# Microcontroller_STM_STM32F373CC.net
KiCad netlist of a schematic drawn in EAGLE
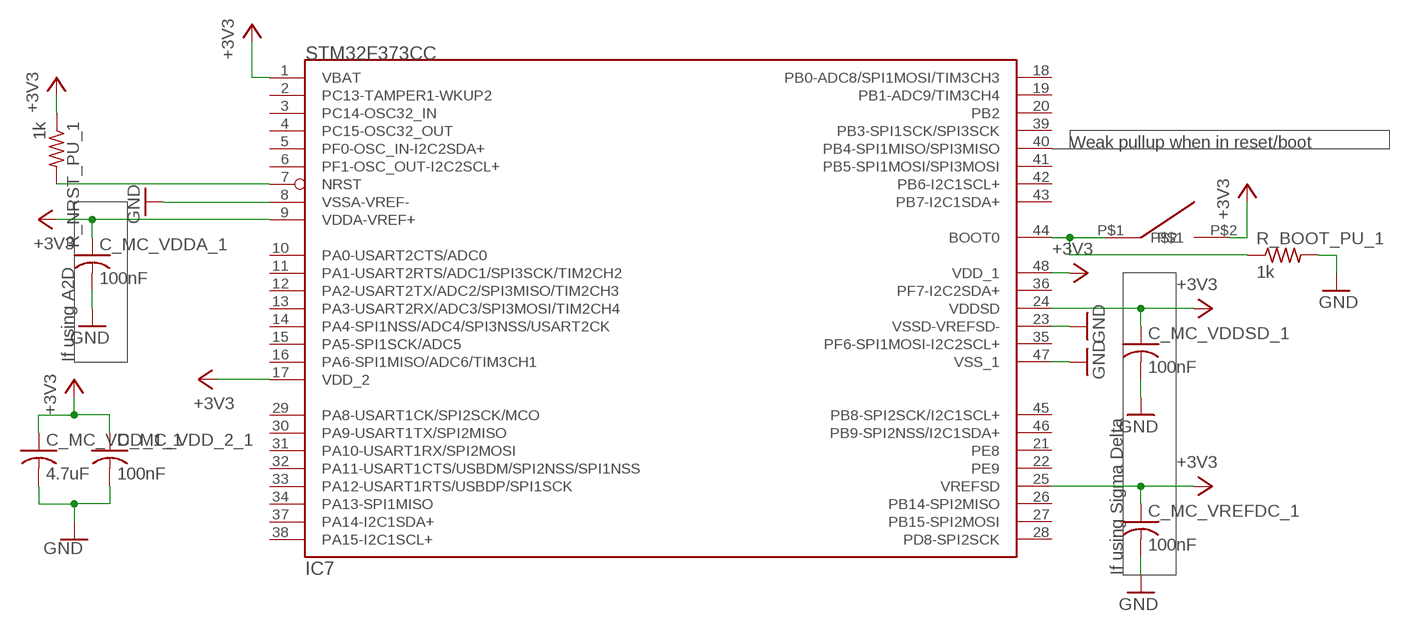
[diagram p0: schematic, sheet 1]

(export (version "E")
  (design (tool "Eeschema 10.0.6"))
  (components
    (comp (ref "C_MC_VDDA_1")
      (value "100nF")
      (footprint "eagle-import:C0603")
      (libsource (lib "eagle-import") (part "C-USC0603"))
    )
    (comp (ref "C_MC_VDDSD_1")
      (value "100nF")
      (footprint "eagle-import:C0603")
      (libsource (lib "eagle-import") (part "C-USC0603"))
    )
    (comp (ref "C_MC_VDD_1_1")
      (value "4.7uF")
      (footprint "eagle-import:C0603")
      (libsource (lib "eagle-import") (part "C-USC0603"))
    )
    (comp (ref "C_MC_VDD_2_1")
      (value "100nF")
      (footprint "eagle-import:C0603")
      (libsource (lib "eagle-import") (part "C-USC0603"))
    )
    (comp (ref "C_MC_VREFDC_1")
      (value "100nF")
      (footprint "eagle-import:C0603")
      (libsource (lib "eagle-import") (part "C-USC0603"))
    )
    (comp (ref "IC7")
      (value "STM32F373CC")
      (footprint "eagle-import:LQFP48")
      (libsource (lib "eagle-import") (part "STM32F373CC"))
    )
    (comp (ref "R_BOOT_PU_1")
      (value "1k")
      (footprint "eagle-import:R0603")
      (libsource (lib "eagle-import") (part "R-US_R0603"))
    )
    (comp (ref "R_NRST_PU_1")
      (value "1k")
      (footprint "eagle-import:R0603")
      (libsource (lib "eagle-import") (part "R-US_R0603"))
    )
    (comp (ref "SW1")
      (value "B3U")
      (footprint "eagle-import:B3U")
      (libsource (lib "eagle-import") (part "B3U"))
    )
  )
  (nets
    (net (code "1") (name "+3V3") (class "Default")
      (node (ref "C_MC_VDDA_1") (pin "1") (pinfunction "1_1") (pintype "passive"))
      (node (ref "C_MC_VDDSD_1") (pin "1") (pinfunction "1_1") (pintype "passive"))
      (node (ref "C_MC_VDD_1_1") (pin "1") (pinfunction "1_1") (pintype "passive"))
      (node (ref "C_MC_VDD_2_1") (pin "1") (pinfunction "1_1") (pintype "passive"))
      (node (ref "C_MC_VREFDC_1") (pin "1") (pinfunction "1_1") (pintype "passive"))
      (node (ref "IC7") (pin "1") (pinfunction "VBAT_1") (pintype "power_in"))
      (node (ref "IC7") (pin "17") (pinfunction "VDD_2_17") (pintype "bidirectional"))
      (node (ref "IC7") (pin "24") (pinfunction "VDDSD_24") (pintype "power_in"))
      (node (ref "IC7") (pin "25") (pinfunction "VREFSD_25") (pintype "bidirectional"))
      (node (ref "IC7") (pin "48") (pinfunction "VDD_1_48") (pintype "power_in"))
      (node (ref "IC7") (pin "9") (pinfunction "VDDA-VREF+_9") (pintype "power_in"))
      (node (ref "R_NRST_PU_1") (pin "1") (pinfunction "1_1") (pintype "passive"))
      (node (ref "SW1") (pin "P$2") (pinfunction "P$2_P$2") (pintype "bidirectional"))
    )
    (net (code "2") (name "GND") (class "Default")
      (node (ref "C_MC_VDDA_1") (pin "2") (pinfunction "2_2") (pintype "passive"))
      (node (ref "C_MC_VDDSD_1") (pin "2") (pinfunction "2_2") (pintype "passive"))
      (node (ref "C_MC_VDD_1_1") (pin "2") (pinfunction "2_2") (pintype "passive"))
      (node (ref "C_MC_VDD_2_1") (pin "2") (pinfunction "2_2") (pintype "passive"))
      (node (ref "C_MC_VREFDC_1") (pin "2") (pinfunction "2_2") (pintype "passive"))
      (node (ref "IC7") (pin "23") (pinfunction "VSSD-VREFSD-_23") (pintype "power_in"))
      (node (ref "IC7") (pin "47") (pinfunction "VSS_1_47") (pintype "power_in"))
      (node (ref "IC7") (pin "8") (pinfunction "VSSA-VREF-_8") (pintype "power_in"))
      (node (ref "R_BOOT_PU_1") (pin "2") (pinfunction "2_2") (pintype "passive"))
    )
    (net (code "3") (name "Net-(IC7-BOOT0)") (class "Default")
      (node (ref "IC7") (pin "44") (pinfunction "BOOT0_44") (pintype "input"))
      (node (ref "R_BOOT_PU_1") (pin "1") (pinfunction "1_1") (pintype "passive"))
      (node (ref "SW1") (pin "P$1") (pinfunction "P$1_P$1") (pintype "bidirectional"))
    )
    (net (code "4") (name "Net-(IC7-NRST)") (class "Default")
      (node (ref "IC7") (pin "7") (pinfunction "NRST_7") (pintype "bidirectional"))
      (node (ref "R_NRST_PU_1") (pin "2") (pinfunction "2_2") (pintype "passive"))
    )
    (net (code "5") (name "unconnected-(IC7-PA0-USART2CTS{slash}ADC0-Pad10)") (class "Default")
      (node (ref "IC7") (pin "10") (pinfunction "PA0-USART2CTS/ADC0_10") (pintype "bidirectional"))
    )
    (net (code "6") (name "unconnected-(IC7-PA1-USART2RTS{slash}ADC1{slash}SPI3SCK{slash}TIM2CH2-Pad11)") (class "Default")
      (node (ref "IC7") (pin "11") (pinfunction "PA1-USART2RTS/ADC1/SPI3SCK/TIM2CH2_11") (pintype "bidirectional"))
    )
    (net (code "7") (name "unconnected-(IC7-PA2-USART2TX{slash}ADC2{slash}SPI3MISO{slash}TIM2CH3-Pad12)") (class "Default")
      (node (ref "IC7") (pin "12") (pinfunction "PA2-USART2TX/ADC2/SPI3MISO/TIM2CH3_12") (pintype "bidirectional"))
    )
    (net (code "8") (name "unconnected-(IC7-PA3-USART2RX{slash}ADC3{slash}SPI3MOSI{slash}TIM2CH4-Pad13)") (class "Default")
      (node (ref "IC7") (pin "13") (pinfunction "PA3-USART2RX/ADC3/SPI3MOSI/TIM2CH4_13") (pintype "bidirectional"))
    )
    (net (code "9") (name "unconnected-(IC7-PA4-SPI1NSS{slash}ADC4{slash}SPI3NSS{slash}USART2CK-Pad14)") (class "Default")
      (node (ref "IC7") (pin "14") (pinfunction "PA4-SPI1NSS/ADC4/SPI3NSS/USART2CK_14") (pintype "bidirectional"))
    )
    (net (code "10") (name "unconnected-(IC7-PA5-SPI1SCK{slash}ADC5-Pad15)") (class "Default")
      (node (ref "IC7") (pin "15") (pinfunction "PA5-SPI1SCK/ADC5_15") (pintype "bidirectional"))
    )
    (net (code "11") (name "unconnected-(IC7-PA6-SPI1MISO{slash}ADC6{slash}TIM3CH1-Pad16)") (class "Default")
      (node (ref "IC7") (pin "16") (pinfunction "PA6-SPI1MISO/ADC6/TIM3CH1_16") (pintype "bidirectional"))
    )
    (net (code "12") (name "unconnected-(IC7-PA8-USART1CK{slash}SPI2SCK{slash}MCO-Pad29)") (class "Default")
      (node (ref "IC7") (pin "29") (pinfunction "PA8-USART1CK/SPI2SCK/MCO_29") (pintype "bidirectional"))
    )
    (net (code "13") (name "unconnected-(IC7-PA9-USART1TX{slash}SPI2MISO-Pad30)") (class "Default")
      (node (ref "IC7") (pin "30") (pinfunction "PA9-USART1TX/SPI2MISO_30") (pintype "bidirectional"))
    )
    (net (code "14") (name "unconnected-(IC7-PA10-USART1RX{slash}SPI2MOSI-Pad31)") (class "Default")
      (node (ref "IC7") (pin "31") (pinfunction "PA10-USART1RX/SPI2MOSI_31") (pintype "bidirectional"))
    )
    (net (code "15") (name "unconnected-(IC7-PA11-USART1CTS{slash}USBDM{slash}SPI2NSS{slash}SPI1NSS-Pad32)") (class "Default")
      (node (ref "IC7") (pin "32") (pinfunction "PA11-USART1CTS/USBDM/SPI2NSS/SPI1NSS_32") (pintype "bidirectional"))
    )
    (net (code "16") (name "unconnected-(IC7-PA12-USART1RTS{slash}USBDP{slash}SPI1SCK-Pad33)") (class "Default")
      (node (ref "IC7") (pin "33") (pinfunction "PA12-USART1RTS/USBDP/SPI1SCK_33") (pintype "bidirectional"))
    )
    (net (code "17") (name "unconnected-(IC7-PA13-SPI1MISO-Pad34)") (class "Default")
      (node (ref "IC7") (pin "34") (pinfunction "PA13-SPI1MISO_34") (pintype "bidirectional"))
    )
    (net (code "18") (name "unconnected-(IC7-PA14-I2C1SDA+-Pad37)") (class "Default")
      (node (ref "IC7") (pin "37") (pinfunction "PA14-I2C1SDA+_37") (pintype "bidirectional"))
    )
    (net (code "19") (name "unconnected-(IC7-PA15-I2C1SCL+-Pad38)") (class "Default")
      (node (ref "IC7") (pin "38") (pinfunction "PA15-I2C1SCL+_38") (pintype "bidirectional"))
    )
    (net (code "20") (name "unconnected-(IC7-PB0-ADC8{slash}SPI1MOSI{slash}TIM3CH3-Pad18)") (class "Default")
      (node (ref "IC7") (pin "18") (pinfunction "PB0-ADC8/SPI1MOSI/TIM3CH3_18") (pintype "bidirectional"))
    )
    (net (code "21") (name "unconnected-(IC7-PB1-ADC9{slash}TIM3CH4-Pad19)") (class "Default")
      (node (ref "IC7") (pin "19") (pinfunction "PB1-ADC9/TIM3CH4_19") (pintype "bidirectional"))
    )
    (net (code "22") (name "unconnected-(IC7-PB2-Pad20)") (class "Default")
      (node (ref "IC7") (pin "20") (pinfunction "PB2_20") (pintype "bidirectional"))
    )
    (net (code "23") (name "unconnected-(IC7-PB3-SPI1SCK{slash}SPI3SCK-Pad39)") (class "Default")
      (node (ref "IC7") (pin "39") (pinfunction "PB3-SPI1SCK/SPI3SCK_39") (pintype "bidirectional"))
    )
    (net (code "24") (name "unconnected-(IC7-PB4-SPI1MISO{slash}SPI3MISO-Pad40)") (class "Default")
      (node (ref "IC7") (pin "40") (pinfunction "PB4-SPI1MISO/SPI3MISO_40") (pintype "bidirectional"))
    )
    (net (code "25") (name "unconnected-(IC7-PB5-SPI1MOSI{slash}SPI3MOSI-Pad41)") (class "Default")
      (node (ref "IC7") (pin "41") (pinfunction "PB5-SPI1MOSI/SPI3MOSI_41") (pintype "bidirectional"))
    )
    (net (code "26") (name "unconnected-(IC7-PB6-I2C1SCL+-Pad42)") (class "Default")
      (node (ref "IC7") (pin "42") (pinfunction "PB6-I2C1SCL+_42") (pintype "bidirectional"))
    )
    (net (code "27") (name "unconnected-(IC7-PB7-I2C1SDA+-Pad43)") (class "Default")
      (node (ref "IC7") (pin "43") (pinfunction "PB7-I2C1SDA+_43") (pintype "bidirectional"))
    )
    (net (code "28") (name "unconnected-(IC7-PB8-SPI2SCK{slash}I2C1SCL+-Pad45)") (class "Default")
      (node (ref "IC7") (pin "45") (pinfunction "PB8-SPI2SCK/I2C1SCL+_45") (pintype "bidirectional"))
    )
    (net (code "29") (name "unconnected-(IC7-PB9-SPI2NSS{slash}I2C1SDA+-Pad46)") (class "Default")
      (node (ref "IC7") (pin "46") (pinfunction "PB9-SPI2NSS/I2C1SDA+_46") (pintype "bidirectional"))
    )
    (net (code "30") (name "unconnected-(IC7-PB14-SPI2MISO-Pad26)") (class "Default")
      (node (ref "IC7") (pin "26") (pinfunction "PB14-SPI2MISO_26") (pintype "bidirectional"))
    )
    (net (code "31") (name "unconnected-(IC7-PB15-SPI2MOSI-Pad27)") (class "Default")
      (node (ref "IC7") (pin "27") (pinfunction "PB15-SPI2MOSI_27") (pintype "bidirectional"))
    )
    (net (code "32") (name "unconnected-(IC7-PC13-TAMPER1-WKUP2-Pad2)") (class "Default")
      (node (ref "IC7") (pin "2") (pinfunction "PC13-TAMPER1-WKUP2_2") (pintype "bidirectional"))
    )
    (net (code "33") (name "unconnected-(IC7-PC14-OSC32_IN-Pad3)") (class "Default")
      (node (ref "IC7") (pin "3") (pinfunction "PC14-OSC32_IN_3") (pintype "bidirectional"))
    )
    (net (code "34") (name "unconnected-(IC7-PC15-OSC32_OUT-Pad4)") (class "Default")
      (node (ref "IC7") (pin "4") (pinfunction "PC15-OSC32_OUT_4") (pintype "bidirectional"))
    )
    (net (code "35") (name "unconnected-(IC7-PD8-SPI2SCK-Pad28)") (class "Default")
      (node (ref "IC7") (pin "28") (pinfunction "PD8-SPI2SCK_28") (pintype "bidirectional"))
    )
    (net (code "36") (name "unconnected-(IC7-PE8-Pad21)") (class "Default")
      (node (ref "IC7") (pin "21") (pinfunction "PE8_21") (pintype "bidirectional"))
    )
    (net (code "37") (name "unconnected-(IC7-PE9-Pad22)") (class "Default")
      (node (ref "IC7") (pin "22") (pinfunction "PE9_22") (pintype "bidirectional"))
    )
    (net (code "38") (name "unconnected-(IC7-PF0-OSC_IN-I2C2SDA+-Pad5)") (class "Default")
      (node (ref "IC7") (pin "5") (pinfunction "PF0-OSC_IN-I2C2SDA+_5") (pintype "bidirectional"))
    )
    (net (code "39") (name "unconnected-(IC7-PF1-OSC_OUT-I2C2SCL+-Pad6)") (class "Default")
      (node (ref "IC7") (pin "6") (pinfunction "PF1-OSC_OUT-I2C2SCL+_6") (pintype "bidirectional"))
    )
    (net (code "40") (name "unconnected-(IC7-PF6-SPI1MOSI-I2C2SCL+-Pad35)") (class "Default")
      (node (ref "IC7") (pin "35") (pinfunction "PF6-SPI1MOSI-I2C2SCL+_35") (pintype "bidirectional"))
    )
    (net (code "41") (name "unconnected-(IC7-PF7-I2C2SDA+-Pad36)") (class "Default")
      (node (ref "IC7") (pin "36") (pinfunction "PF7-I2C2SDA+_36") (pintype "bidirectional"))
    )
  )
)
